# iiitduino.net
KiCad netlist of a schematic drawn in EAGLE
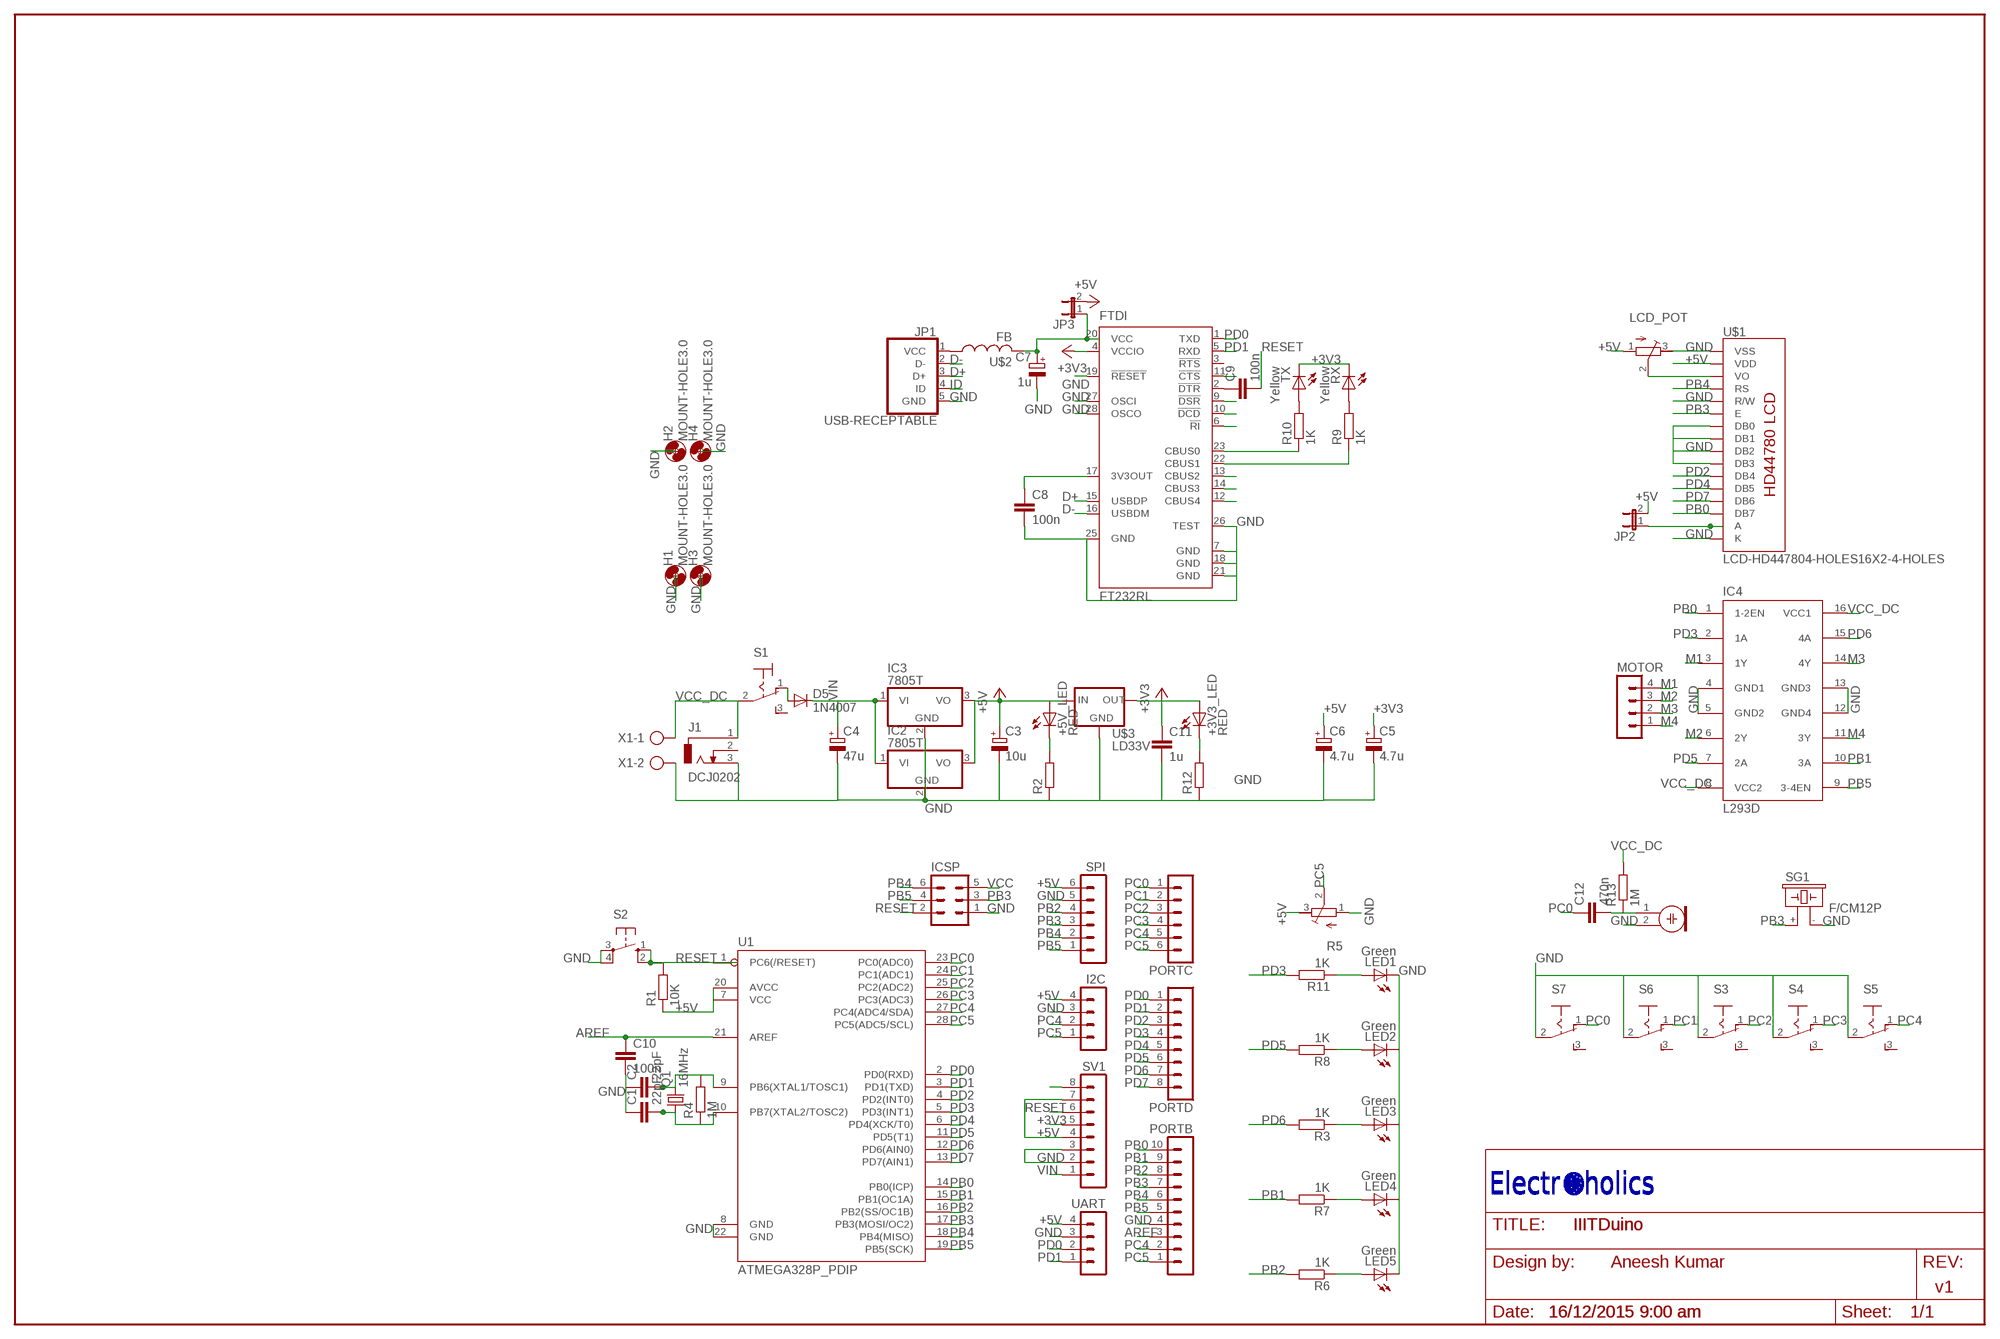
[diagram p0: schematic, sheet 1]

(export (version "E")
  (design (tool "Eeschema 10.0.6"))
  (components
    (comp (ref "+3V3_LED")
      (value "RED")
      (footprint "eagle-import:LED3MM")
      (libsource (lib "eagle-import") (part "LED3MM"))
    )
    (comp (ref "+5V_LED")
      (value "RED")
      (footprint "eagle-import:LED3MM")
      (libsource (lib "eagle-import") (part "LED3MM"))
    )
    (comp (ref "C1")
      (value "22pF")
      (footprint "eagle-import:C025-025X050")
      (libsource (lib "eagle-import") (part "C-EU025-025X050"))
    )
    (comp (ref "C2")
      (value "22pF")
      (footprint "eagle-import:C025-025X050")
      (libsource (lib "eagle-import") (part "C-EU025-025X050"))
    )
    (comp (ref "C3")
      (value "10u")
      (footprint "eagle-import:E2,5-6")
      (libsource (lib "eagle-import") (part "CPOL-EUE2.5-6"))
    )
    (comp (ref "C4")
      (value "47u")
      (footprint "eagle-import:E5-10,5")
      (libsource (lib "eagle-import") (part "CPOL-EUE5-10.5"))
    )
    (comp (ref "C5")
      (value "4.7u")
      (footprint "eagle-import:E2,5-6")
      (libsource (lib "eagle-import") (part "CPOL-EUE2.5-6"))
    )
    (comp (ref "C6")
      (value "4.7u")
      (footprint "eagle-import:E2,5-6")
      (libsource (lib "eagle-import") (part "CPOL-EUE2.5-6"))
    )
    (comp (ref "C7")
      (value "1u")
      (footprint "eagle-import:E2,5-6")
      (libsource (lib "eagle-import") (part "CPOL-EUE2.5-6"))
    )
    (comp (ref "C8")
      (value "100n")
      (footprint "eagle-import:C025-025X050")
      (libsource (lib "eagle-import") (part "C-EU025-025X050"))
    )
    (comp (ref "C9")
      (value "100n")
      (footprint "eagle-import:C025-025X050")
      (libsource (lib "eagle-import") (part "C-EU025-025X050"))
    )
    (comp (ref "C10")
      (value "100n")
      (footprint "eagle-import:C025-025X050")
      (libsource (lib "eagle-import") (part "C-EU025-025X050"))
    )
    (comp (ref "C11")
      (value "1u")
      (footprint "eagle-import:C025-025X050")
      (libsource (lib "eagle-import") (part "C-EU025-025X050"))
    )
    (comp (ref "C12")
      (value "470n")
      (footprint "eagle-import:C025-025X050")
      (libsource (lib "eagle-import") (part "C-EU025-025X050"))
    )
    (comp (ref "D5")
      (value "1N4007")
      (footprint "eagle-import:DO41-10")
      (libsource (lib "eagle-import") (part "1N4004"))
    )
    (comp (ref "FTDI")
      (value "FT232RL")
      (footprint "eagle-import:SSOP28")
      (libsource (lib "eagle-import") (part "FT232RL"))
    )
    (comp (ref "H1")
      (value "MOUNT-HOLE3.0")
      (footprint "eagle-import:3,0")
      (libsource (lib "eagle-import") (part "MOUNT-HOLE3.0"))
    )
    (comp (ref "H2")
      (value "MOUNT-HOLE3.0")
      (footprint "eagle-import:3,0")
      (libsource (lib "eagle-import") (part "MOUNT-HOLE3.0"))
    )
    (comp (ref "H3")
      (value "MOUNT-HOLE3.0")
      (footprint "eagle-import:3,0")
      (libsource (lib "eagle-import") (part "MOUNT-HOLE3.0"))
    )
    (comp (ref "H4")
      (value "MOUNT-HOLE3.0")
      (footprint "eagle-import:3,0")
      (libsource (lib "eagle-import") (part "MOUNT-HOLE3.0"))
    )
    (comp (ref "I2C")
      (value "MA04-1")
      (footprint "eagle-import:MA04-1")
      (libsource (lib "eagle-import") (part "MA04-1"))
    )
    (comp (ref "IC2")
      (value "7805T")
      (footprint "eagle-import:TO220H")
      (libsource (lib "eagle-import") (part "78T05"))
    )
    (comp (ref "IC3")
      (value "7805T")
      (footprint "eagle-import:TO220H")
      (libsource (lib "eagle-import") (part "78T05"))
    )
    (comp (ref "IC4")
      (value "L293D")
      (footprint "eagle-import:DIL16")
      (libsource (lib "eagle-import") (part "L293D"))
    )
    (comp (ref "ICSP")
      (value "MA03-2")
      (footprint "eagle-import:MA03-2")
      (libsource (lib "eagle-import") (part "MA03-2"))
    )
    (comp (ref "J1")
      (value "DCJ0202")
      (footprint "eagle-import:DCJ0202")
      (libsource (lib "eagle-import") (part "DCJ0202"))
    )
    (comp (ref "JP1")
      (value "USB-RECEPTABLE")
      (footprint "eagle-import:FCI-10103594-0001LF")
      (libsource (lib "eagle-import") (part "USB-RECEPTABLE"))
    )
    (comp (ref "JP2")
      (value "JP1E")
      (footprint "eagle-import:JP1")
      (libsource (lib "eagle-import") (part "JP1E"))
    )
    (comp (ref "JP3")
      (value "JP1E")
      (footprint "eagle-import:JP1")
      (libsource (lib "eagle-import") (part "JP1E"))
    )
    (comp (ref "LCD_POT")
      (value "R-TRIMM64W")
      (footprint "eagle-import:RTRIM64W")
      (libsource (lib "eagle-import") (part "R-TRIMM64W"))
    )
    (comp (ref "LED1")
      (value "Green")
      (footprint "eagle-import:LED3MM")
      (libsource (lib "eagle-import") (part "LED3MM"))
    )
    (comp (ref "LED2")
      (value "Green")
      (footprint "eagle-import:LED3MM")
      (libsource (lib "eagle-import") (part "LED3MM"))
    )
    (comp (ref "LED3")
      (value "Green")
      (footprint "eagle-import:LED3MM")
      (libsource (lib "eagle-import") (part "LED3MM"))
    )
    (comp (ref "LED4")
      (value "Green")
      (footprint "eagle-import:LED3MM")
      (libsource (lib "eagle-import") (part "LED3MM"))
    )
    (comp (ref "LED5")
      (value "Green")
      (footprint "eagle-import:LED3MM")
      (libsource (lib "eagle-import") (part "LED3MM"))
    )
    (comp (ref "M1")
      (value "ELECTRET_MICROPHON-F6050AP")
      (footprint "eagle-import:F6050AP")
      (libsource (lib "eagle-import") (part "ELECTRET_MICROPHON-F6050AP"))
    )
    (comp (ref "MOTOR")
      (value "MA04-1")
      (footprint "eagle-import:MA04-1")
      (libsource (lib "eagle-import") (part "MA04-1"))
    )
    (comp (ref "PORTB")
      (value "MA10-1W")
      (footprint "eagle-import:MA10-1W")
      (libsource (lib "eagle-import") (part "MA10-1W"))
    )
    (comp (ref "PORTC")
      (value "MA06-1")
      (footprint "eagle-import:MA06-1")
      (libsource (lib "eagle-import") (part "MA06-1"))
    )
    (comp (ref "PORTD")
      (value "MA08-1")
      (footprint "eagle-import:MA08-1")
      (libsource (lib "eagle-import") (part "MA08-1"))
    )
    (comp (ref "Q1")
      (value "16MHz")
      (footprint "eagle-import:HC49U70")
      (libsource (lib "eagle-import") (part "CRYSTALHC49U70"))
    )
    (comp (ref "R1")
      (value "10K")
      (footprint "eagle-import:0207_10")
      (libsource (lib "eagle-import") (part "R-EU_0207/10"))
    )
    (comp (ref "R2")
      (value "R-EU_0207/7")
      (footprint "eagle-import:0207_7")
      (libsource (lib "eagle-import") (part "R-EU_0207/7"))
    )
    (comp (ref "R3")
      (value "1K")
      (footprint "eagle-import:0207_10")
      (libsource (lib "eagle-import") (part "R-EU_0207/10"))
    )
    (comp (ref "R4")
      (value "1M")
      (footprint "eagle-import:0207_10")
      (libsource (lib "eagle-import") (part "R-EU_0207/10"))
    )
    (comp (ref "R5")
      (value "R-TRIMM64W")
      (footprint "eagle-import:RTRIM64W")
      (libsource (lib "eagle-import") (part "R-TRIMM64W"))
    )
    (comp (ref "R6")
      (value "1K")
      (footprint "eagle-import:0207_10")
      (libsource (lib "eagle-import") (part "R-EU_0207/10"))
    )
    (comp (ref "R7")
      (value "1K")
      (footprint "eagle-import:0207_10")
      (libsource (lib "eagle-import") (part "R-EU_0207/10"))
    )
    (comp (ref "R8")
      (value "1K")
      (footprint "eagle-import:0207_10")
      (libsource (lib "eagle-import") (part "R-EU_0207/10"))
    )
    (comp (ref "R9")
      (value "1K")
      (footprint "eagle-import:0207_7")
      (libsource (lib "eagle-import") (part "R-EU_0207/7"))
    )
    (comp (ref "R10")
      (value "1K")
      (footprint "eagle-import:0207_7")
      (libsource (lib "eagle-import") (part "R-EU_0207/7"))
    )
    (comp (ref "R11")
      (value "1K")
      (footprint "eagle-import:0207_10")
      (libsource (lib "eagle-import") (part "R-EU_0207/10"))
    )
    (comp (ref "R12")
      (value "R-EU_0207/7")
      (footprint "eagle-import:0207_7")
      (libsource (lib "eagle-import") (part "R-EU_0207/7"))
    )
    (comp (ref "R13")
      (value "1M")
      (footprint "eagle-import:0207_10")
      (libsource (lib "eagle-import") (part "R-EU_0207/10"))
    )
    (comp (ref "RX")
      (value "Yellow")
      (footprint "eagle-import:LED3MM")
      (libsource (lib "eagle-import") (part "LED3MM"))
    )
    (comp (ref "S1")
      (value "320-916")
      (footprint "eagle-import:320-916")
      (libsource (lib "eagle-import") (part "320-916"))
    )
    (comp (ref "S2")
      (value "10-XX")
      (footprint "eagle-import:B3F-10XX")
      (fields (field (name "MPN") "B3F-1000"))
      (libsource (lib "eagle-import") (part "10-XX"))
    )
    (comp (ref "S3")
      (value "255SB")
      (footprint "eagle-import:255SB")
      (libsource (lib "eagle-import") (part "255SB"))
    )
    (comp (ref "S4")
      (value "255SB")
      (footprint "eagle-import:255SB")
      (libsource (lib "eagle-import") (part "255SB"))
    )
    (comp (ref "S5")
      (value "255SB")
      (footprint "eagle-import:255SB")
      (libsource (lib "eagle-import") (part "255SB"))
    )
    (comp (ref "S6")
      (value "255SB")
      (footprint "eagle-import:255SB")
      (libsource (lib "eagle-import") (part "255SB"))
    )
    (comp (ref "S7")
      (value "255SB")
      (footprint "eagle-import:255SB")
      (libsource (lib "eagle-import") (part "255SB"))
    )
    (comp (ref "SG1")
      (value "F/CM12P")
      (footprint "eagle-import:F_CM12P")
      (libsource (lib "eagle-import") (part "F/CM12P"))
    )
    (comp (ref "SPI")
      (value "MA06-1")
      (footprint "eagle-import:MA06-1")
      (libsource (lib "eagle-import") (part "MA06-1"))
    )
    (comp (ref "SV1")
      (value "MA08-1")
      (footprint "eagle-import:MA08-1")
      (libsource (lib "eagle-import") (part "MA08-1"))
    )
    (comp (ref "TX")
      (value "Yellow")
      (footprint "eagle-import:LED3MM")
      (libsource (lib "eagle-import") (part "LED3MM"))
    )
    (comp (ref "U$1")
      (value "LCD-HD447804-HOLES16X2-4-HOLES")
      (footprint "eagle-import:LCD-16X2-4HOLES")
      (libsource (lib "eagle-import") (part "LCD-HD4478016X2-4-HOLES4-HOLES"))
    )
    (comp (ref "U$2") (value "FB") (footprint "eagle-import:FB") (libsource (lib "eagle-import") (part "FB")))
    (comp (ref "U$3")
      (value "LD33V")
      (footprint "eagle-import:TO-220")
      (libsource (lib "eagle-import") (part "LD33V"))
    )
    (comp (ref "U1")
      (value "ATMEGA328P_PDIP")
      (footprint "eagle-import:DIL28-3")
      (libsource (lib "eagle-import") (part "ATMEGA328P_PDIP"))
    )
    (comp (ref "UART")
      (value "MA04-1")
      (footprint "eagle-import:MA04-1")
      (libsource (lib "eagle-import") (part "MA04-1"))
    )
    (comp (ref "X1")
      (value "AK300/2")
      (footprint "eagle-import:AK300_2")
      (libsource (lib "eagle-import") (part "AK300/2"))
    )
  )
  (nets
    (net (code "1") (name "+3V3") (class "Default")
      (node (ref "+3V3_LED") (pin "A") (pinfunction "A_A") (pintype "passive"))
      (node (ref "C11") (pin "1") (pinfunction "1_1") (pintype "passive"))
      (node (ref "C5") (pin "+") (pinfunction "+_+") (pintype "passive"))
      (node (ref "FTDI") (pin "4") (pinfunction "VCCIO_4") (pintype "power_in"))
      (node (ref "RX") (pin "K") (pinfunction "C_K") (pintype "passive"))
      (node (ref "SV1") (pin "5") (pinfunction "5_5") (pintype "passive"))
      (node (ref "TX") (pin "K") (pinfunction "C_K") (pintype "passive"))
      (node (ref "U$3") (pin "2") (pinfunction "OUT_2") (pintype "passive"))
    )
    (net (code "2") (name "+5V") (class "Default")
      (node (ref "+5V_LED") (pin "A") (pinfunction "A_A") (pintype "passive"))
      (node (ref "C3") (pin "+") (pinfunction "+_+") (pintype "passive"))
      (node (ref "C6") (pin "+") (pinfunction "+_+") (pintype "passive"))
      (node (ref "C7") (pin "+") (pinfunction "+_+") (pintype "passive"))
      (node (ref "FTDI") (pin "20") (pinfunction "VCC_20") (pintype "power_in"))
      (node (ref "I2C") (pin "4") (pinfunction "4_4") (pintype "passive"))
      (node (ref "IC2") (pin "3") (pinfunction "VO_3") (pintype "passive"))
      (node (ref "IC3") (pin "3") (pinfunction "VO_3") (pintype "passive"))
      (node (ref "JP2") (pin "2") (pinfunction "2_2") (pintype "passive"))
      (node (ref "JP3") (pin "1") (pinfunction "1_1") (pintype "passive"))
      (node (ref "JP3") (pin "2") (pinfunction "2_2") (pintype "passive"))
      (node (ref "LCD_POT") (pin "1") (pinfunction "A_1") (pintype "passive"))
      (node (ref "R1") (pin "1") (pinfunction "1_1") (pintype "passive"))
      (node (ref "R5") (pin "3") (pinfunction "E_3") (pintype "passive"))
      (node (ref "SPI") (pin "6") (pinfunction "6_6") (pintype "passive"))
      (node (ref "SV1") (pin "4") (pinfunction "4_4") (pintype "passive"))
      (node (ref "SV1") (pin "7") (pinfunction "7_7") (pintype "passive"))
      (node (ref "U$1") (pin "2") (pinfunction "VDD_2") (pintype "power_in"))
      (node (ref "U$2") (pin "P$2") (pinfunction "2_P$2") (pintype "passive"))
      (node (ref "U$3") (pin "3") (pinfunction "IN_3") (pintype "input"))
      (node (ref "U1") (pin "20") (pinfunction "AVCC_20") (pintype "bidirectional"))
      (node (ref "U1") (pin "7") (pinfunction "VCC_7") (pintype "bidirectional"))
      (node (ref "UART") (pin "4") (pinfunction "4_4") (pintype "passive"))
    )
    (net (code "3") (name "/AREF") (class "Default")
      (node (ref "C10") (pin "1") (pinfunction "1_1") (pintype "passive"))
      (node (ref "PORTB") (pin "3") (pinfunction "3_3") (pintype "passive"))
      (node (ref "U1") (pin "21") (pinfunction "AREF_21") (pintype "bidirectional"))
    )
    (net (code "4") (name "/D+") (class "Default")
      (node (ref "FTDI") (pin "15") (pinfunction "USBDP_15") (pintype "bidirectional"))
      (node (ref "JP1") (pin "3") (pinfunction "D+_3") (pintype "bidirectional"))
    )
    (net (code "5") (name "/D-") (class "Default")
      (node (ref "FTDI") (pin "16") (pinfunction "USBDM_16") (pintype "bidirectional"))
      (node (ref "JP1") (pin "2") (pinfunction "D-_2") (pintype "bidirectional"))
    )
    (net (code "6") (name "/GND") (class "Default")
      (node (ref "C1") (pin "1") (pinfunction "1_1") (pintype "passive"))
      (node (ref "C10") (pin "2") (pinfunction "2_2") (pintype "passive"))
      (node (ref "C11") (pin "2") (pinfunction "2_2") (pintype "passive"))
      (node (ref "C2") (pin "1") (pinfunction "1_1") (pintype "passive"))
      (node (ref "C3") (pin "-") (pinfunction "-_-") (pintype "passive"))
      (node (ref "C4") (pin "-") (pinfunction "-_-") (pintype "passive"))
      (node (ref "C5") (pin "-") (pinfunction "-_-") (pintype "passive"))
      (node (ref "C6") (pin "-") (pinfunction "-_-") (pintype "passive"))
      (node (ref "C7") (pin "-") (pinfunction "-_-") (pintype "passive"))
      (node (ref "C8") (pin "2") (pinfunction "2_2") (pintype "passive"))
      (node (ref "FTDI") (pin "10") (pinfunction "~{DCD}_10") (pintype "input"))
      (node (ref "FTDI") (pin "11") (pinfunction "~{CTS}_11") (pintype "input"))
      (node (ref "FTDI") (pin "12") (pinfunction "CBUS4_12") (pintype "bidirectional"))
      (node (ref "FTDI") (pin "13") (pinfunction "CBUS2_13") (pintype "bidirectional"))
      (node (ref "FTDI") (pin "14") (pinfunction "CBUS3_14") (pintype "bidirectional"))
      (node (ref "FTDI") (pin "18") (pinfunction "GND_18") (pintype "power_in"))
      (node (ref "FTDI") (pin "19") (pinfunction "~{RESET}_19") (pintype "input"))
      (node (ref "FTDI") (pin "21") (pinfunction "GND_21") (pintype "power_in"))
      (node (ref "FTDI") (pin "25") (pinfunction "GND_25") (pintype "power_in"))
      (node (ref "FTDI") (pin "26") (pinfunction "TEST_26") (pintype "input"))
      (node (ref "FTDI") (pin "27") (pinfunction "OSCI_27") (pintype "input"))
      (node (ref "FTDI") (pin "28") (pinfunction "OSCO_28") (pintype "output"))
      (node (ref "FTDI") (pin "6") (pinfunction "~{RI}_6") (pintype "input"))
      (node (ref "FTDI") (pin "7") (pinfunction "GND_7") (pintype "power_in"))
      (node (ref "FTDI") (pin "9") (pinfunction "~{DSR}_9") (pintype "input"))
      (node (ref "I2C") (pin "3") (pinfunction "3_3") (pintype "passive"))
      (node (ref "IC2") (pin "2") (pinfunction "GND_2") (pintype "passive"))
      (node (ref "IC3") (pin "2") (pinfunction "GND_2") (pintype "passive"))
      (node (ref "IC4") (pin "12") (pinfunction "GND4_12") (pintype "power_in"))
      (node (ref "IC4") (pin "13") (pinfunction "GND3_13") (pintype "power_in"))
      (node (ref "IC4") (pin "4") (pinfunction "GND1_4") (pintype "power_in"))
      (node (ref "IC4") (pin "5") (pinfunction "GND2_5") (pintype "power_in"))
      (node (ref "ICSP") (pin "1") (pinfunction "1_1") (pintype "passive"))
      (node (ref "J1") (pin "3") (pinfunction "3_3") (pintype "passive"))
      (node (ref "JP1") (pin "5") (pinfunction "GND_5") (pintype "bidirectional"))
      (node (ref "LCD_POT") (pin "3") (pinfunction "E_3") (pintype "passive"))
      (node (ref "LED1") (pin "K") (pinfunction "C_K") (pintype "passive"))
      (node (ref "LED2") (pin "K") (pinfunction "C_K") (pintype "passive"))
      (node (ref "LED3") (pin "K") (pinfunction "C_K") (pintype "passive"))
      (node (ref "LED4") (pin "K") (pinfunction "C_K") (pintype "passive"))
      (node (ref "LED5") (pin "K") (pinfunction "C_K") (pintype "passive"))
      (node (ref "M1") (pin "2") (pinfunction "2_2") (pintype "passive"))
      (node (ref "PORTB") (pin "4") (pinfunction "4_4") (pintype "passive"))
      (node (ref "R12") (pin "1") (pinfunction "1_1") (pintype "passive"))
      (node (ref "R2") (pin "1") (pinfunction "1_1") (pintype "passive"))
      (node (ref "R5") (pin "1") (pinfunction "A_1") (pintype "passive"))
      (node (ref "S2") (pin "3") (pinfunction "P_3") (pintype "passive"))
      (node (ref "S2") (pin "4") (pinfunction "P1_4") (pintype "passive"))
      (node (ref "S3") (pin "2") (pinfunction "P_2") (pintype "passive"))
      (node (ref "S4") (pin "2") (pinfunction "P_2") (pintype "passive"))
      (node (ref "S5") (pin "2") (pinfunction "P_2") (pintype "passive"))
      (node (ref "S6") (pin "2") (pinfunction "P_2") (pintype "passive"))
      (node (ref "S7") (pin "2") (pinfunction "P_2") (pintype "passive"))
      (node (ref "SG1") (pin "-") (pinfunction "2_-") (pintype "passive"))
      (node (ref "SPI") (pin "5") (pinfunction "5_5") (pintype "passive"))
      (node (ref "SV1") (pin "2") (pinfunction "2_2") (pintype "passive"))
      (node (ref "SV1") (pin "3") (pinfunction "3_3") (pintype "passive"))
      (node (ref "U$1") (pin "1") (pinfunction "VSS_1") (pintype "power_in"))
      (node (ref "U$1") (pin "10") (pinfunction "DB3_10") (pintype "bidirectional"))
      (node (ref "U$1") (pin "16") (pinfunction "K_16") (pintype "power_in"))
      (node (ref "U$1") (pin "5") (pinfunction "R/W_5") (pintype "input"))
      (node (ref "U$1") (pin "7") (pinfunction "DB0_7") (pintype "bidirectional"))
      (node (ref "U$1") (pin "8") (pinfunction "DB1_8") (pintype "bidirectional"))
      (node (ref "U$1") (pin "9") (pinfunction "DB2_9") (pintype "bidirectional"))
      (node (ref "U$3") (pin "1") (pinfunction "GND_1") (pintype "input"))
      (node (ref "U1") (pin "22") (pinfunction "GND_22") (pintype "bidirectional"))
      (node (ref "U1") (pin "8") (pinfunction "GND_8") (pintype "bidirectional"))
      (node (ref "UART") (pin "3") (pinfunction "3_3") (pintype "passive"))
      (node (ref "X1") (pin "2") (pinfunction "KL_2") (pintype "passive"))
    )
    (net (code "7") (name "/ID") (class "Default")
      (node (ref "JP1") (pin "4") (pinfunction "ID_4") (pintype "bidirectional"))
    )
    (net (code "8") (name "/M1") (class "Default")
      (node (ref "IC4") (pin "3") (pinfunction "1Y_3") (pintype "output"))
      (node (ref "MOTOR") (pin "4") (pinfunction "4_4") (pintype "passive"))
    )
    (net (code "9") (name "/M2") (class "Default")
      (node (ref "IC4") (pin "6") (pinfunction "2Y_6") (pintype "output"))
      (node (ref "MOTOR") (pin "3") (pinfunction "3_3") (pintype "passive"))
    )
    (net (code "10") (name "/M3") (class "Default")
      (node (ref "IC4") (pin "14") (pinfunction "4Y_14") (pintype "output"))
      (node (ref "MOTOR") (pin "2") (pinfunction "2_2") (pintype "passive"))
    )
    (net (code "11") (name "/M4") (class "Default")
      (node (ref "IC4") (pin "11") (pinfunction "3Y_11") (pintype "output"))
      (node (ref "MOTOR") (pin "1") (pinfunction "1_1") (pintype "passive"))
    )
    (net (code "12") (name "/PB0") (class "Default")
      (node (ref "IC4") (pin "1") (pinfunction "1-2EN_1") (pintype "input"))
      (node (ref "PORTB") (pin "10") (pinfunction "10_10") (pintype "passive"))
      (node (ref "U$1") (pin "14") (pinfunction "DB7_14") (pintype "bidirectional"))
      (node (ref "U1") (pin "14") (pinfunction "PB0(ICP)_14") (pintype "bidirectional"))
    )
    (net (code "13") (name "/PB1") (class "Default")
      (node (ref "IC4") (pin "10") (pinfunction "3A_10") (pintype "input"))
      (node (ref "PORTB") (pin "9") (pinfunction "9_9") (pintype "passive"))
      (node (ref "R7") (pin "2") (pinfunction "2_2") (pintype "passive"))
      (node (ref "U1") (pin "15") (pinfunction "PB1(OC1A)_15") (pintype "bidirectional"))
    )
    (net (code "14") (name "/PB2") (class "Default")
      (node (ref "PORTB") (pin "8") (pinfunction "8_8") (pintype "passive"))
      (node (ref "R6") (pin "2") (pinfunction "2_2") (pintype "passive"))
      (node (ref "SPI") (pin "4") (pinfunction "4_4") (pintype "passive"))
      (node (ref "U1") (pin "16") (pinfunction "PB2(SS/OC1B)_16") (pintype "bidirectional"))
    )
    (net (code "15") (name "/PB3") (class "Default")
      (node (ref "ICSP") (pin "3") (pinfunction "3_3") (pintype "passive"))
      (node (ref "PORTB") (pin "7") (pinfunction "7_7") (pintype "passive"))
      (node (ref "SG1") (pin "+") (pinfunction "1_+") (pintype "passive"))
      (node (ref "SPI") (pin "3") (pinfunction "3_3") (pintype "passive"))
      (node (ref "U$1") (pin "6") (pinfunction "E_6") (pintype "input"))
      (node (ref "U1") (pin "17") (pinfunction "PB3(MOSI/OC2)_17") (pintype "bidirectional"))
    )
    (net (code "16") (name "/PB4") (class "Default")
      (node (ref "ICSP") (pin "6") (pinfunction "6_6") (pintype "passive"))
      (node (ref "PORTB") (pin "6") (pinfunction "6_6") (pintype "passive"))
      (node (ref "SPI") (pin "2") (pinfunction "2_2") (pintype "passive"))
      (node (ref "U$1") (pin "4") (pinfunction "RS_4") (pintype "input"))
      (node (ref "U1") (pin "18") (pinfunction "PB4(MISO)_18") (pintype "bidirectional"))
    )
    (net (code "17") (name "/PB5") (class "Default")
      (node (ref "IC4") (pin "9") (pinfunction "3-4EN_9") (pintype "input"))
      (node (ref "ICSP") (pin "4") (pinfunction "4_4") (pintype "passive"))
      (node (ref "PORTB") (pin "5") (pinfunction "5_5") (pintype "passive"))
      (node (ref "SPI") (pin "1") (pinfunction "1_1") (pintype "passive"))
      (node (ref "U1") (pin "19") (pinfunction "PB5(SCK)_19") (pintype "bidirectional"))
    )
    (net (code "18") (name "/PC0") (class "Default")
      (node (ref "C12") (pin "1") (pinfunction "1_1") (pintype "passive"))
      (node (ref "PORTC") (pin "1") (pinfunction "1_1") (pintype "passive"))
      (node (ref "S7") (pin "1") (pinfunction "O_1") (pintype "passive"))
      (node (ref "U1") (pin "23") (pinfunction "PC0(ADC0)_23") (pintype "bidirectional"))
    )
    (net (code "19") (name "/PC1") (class "Default")
      (node (ref "PORTC") (pin "2") (pinfunction "2_2") (pintype "passive"))
      (node (ref "S6") (pin "1") (pinfunction "O_1") (pintype "passive"))
      (node (ref "U1") (pin "24") (pinfunction "PC1(ADC1)_24") (pintype "bidirectional"))
    )
    (net (code "20") (name "/PC2") (class "Default")
      (node (ref "PORTC") (pin "3") (pinfunction "3_3") (pintype "passive"))
      (node (ref "S3") (pin "1") (pinfunction "O_1") (pintype "passive"))
      (node (ref "U1") (pin "25") (pinfunction "PC2(ADC2)_25") (pintype "bidirectional"))
    )
    (net (code "21") (name "/PC3") (class "Default")
      (node (ref "PORTC") (pin "4") (pinfunction "4_4") (pintype "passive"))
      (node (ref "S4") (pin "1") (pinfunction "O_1") (pintype "passive"))
      (node (ref "U1") (pin "26") (pinfunction "PC3(ADC3)_26") (pintype "bidirectional"))
    )
    (net (code "22") (name "/PC4") (class "Default")
      (node (ref "I2C") (pin "2") (pinfunction "2_2") (pintype "passive"))
      (node (ref "PORTB") (pin "2") (pinfunction "2_2") (pintype "passive"))
      (node (ref "PORTC") (pin "5") (pinfunction "5_5") (pintype "passive"))
      (node (ref "S5") (pin "1") (pinfunction "O_1") (pintype "passive"))
      (node (ref "U1") (pin "27") (pinfunction "PC4(ADC4/SDA)_27") (pintype "bidirectional"))
    )
    (net (code "23") (name "/PC5") (class "Default")
      (node (ref "I2C") (pin "1") (pinfunction "1_1") (pintype "passive"))
      (node (ref "PORTB") (pin "1") (pinfunction "1_1") (pintype "passive"))
      (node (ref "PORTC") (pin "6") (pinfunction "6_6") (pintype "passive"))
      (node (ref "R5") (pin "2") (pinfunction "S_2") (pintype "passive"))
      (node (ref "U1") (pin "28") (pinfunction "PC5(ADC5/SCL)_28") (pintype "bidirectional"))
    )
    (net (code "24") (name "/PD0") (class "Default")
      (node (ref "FTDI") (pin "1") (pinfunction "TXD_1") (pintype "output"))
      (node (ref "PORTD") (pin "1") (pinfunction "1_1") (pintype "passive"))
      (node (ref "U1") (pin "2") (pinfunction "PD0(RXD)_2") (pintype "bidirectional"))
      (node (ref "UART") (pin "2") (pinfunction "2_2") (pintype "passive"))
    )
    (net (code "25") (name "/PD1") (class "Default")
      (node (ref "FTDI") (pin "5") (pinfunction "RXD_5") (pintype "input"))
      (node (ref "PORTD") (pin "2") (pinfunction "2_2") (pintype "passive"))
      (node (ref "U1") (pin "3") (pinfunction "PD1(TXD)_3") (pintype "bidirectional"))
      (node (ref "UART") (pin "1") (pinfunction "1_1") (pintype "passive"))
    )
    (net (code "26") (name "/PD2") (class "Default")
      (node (ref "PORTD") (pin "3") (pinfunction "3_3") (pintype "passive"))
      (node (ref "U$1") (pin "11") (pinfunction "DB4_11") (pintype "bidirectional"))
      (node (ref "U1") (pin "4") (pinfunction "PD2(INT0)_4") (pintype "bidirectional"))
    )
    (net (code "27") (name "/PD3") (class "Default")
      (node (ref "IC4") (pin "2") (pinfunction "1A_2") (pintype "input"))
      (node (ref "PORTD") (pin "4") (pinfunction "4_4") (pintype "passive"))
      (node (ref "R11") (pin "2") (pinfunction "2_2") (pintype "passive"))
      (node (ref "U1") (pin "5") (pinfunction "PD3(INT1)_5") (pintype "bidirectional"))
    )
    (net (code "28") (name "/PD4") (class "Default")
      (node (ref "PORTD") (pin "5") (pinfunction "5_5") (pintype "passive"))
      (node (ref "U$1") (pin "12") (pinfunction "DB5_12") (pintype "bidirectional"))
      (node (ref "U1") (pin "6") (pinfunction "PD4(XCK/T0)_6") (pintype "bidirectional"))
    )
    (net (code "29") (name "/PD5") (class "Default")
      (node (ref "IC4") (pin "7") (pinfunction "2A_7") (pintype "input"))
      (node (ref "PORTD") (pin "6") (pinfunction "6_6") (pintype "passive"))
      (node (ref "R8") (pin "2") (pinfunction "2_2") (pintype "passive"))
      (node (ref "U1") (pin "11") (pinfunction "PD5(T1)_11") (pintype "bidirectional"))
    )
    (net (code "30") (name "/PD6") (class "Default")
      (node (ref "IC4") (pin "15") (pinfunction "4A_15") (pintype "input"))
      (node (ref "PORTD") (pin "7") (pinfunction "7_7") (pintype "passive"))
      (node (ref "R3") (pin "2") (pinfunction "2_2") (pintype "passive"))
      (node (ref "U1") (pin "12") (pinfunction "PD6(AIN0)_12") (pintype "bidirectional"))
    )
    (net (code "31") (name "/PD7") (class "Default")
      (node (ref "PORTD") (pin "8") (pinfunction "8_8") (pintype "passive"))
      (node (ref "U$1") (pin "13") (pinfunction "DB6_13") (pintype "bidirectional"))
      (node (ref "U1") (pin "13") (pinfunction "PD7(AIN1)_13") (pintype "bidirectional"))
    )
    (net (code "32") (name "/RESET") (class "Default")
      (node (ref "C9") (pin "2") (pinfunction "2_2") (pintype "passive"))
      (node (ref "ICSP") (pin "2") (pinfunction "2_2") (pintype "passive"))
      (node (ref "R1") (pin "2") (pinfunction "2_2") (pintype "passive"))
      (node (ref "S2") (pin "1") (pinfunction "S_1") (pintype "passive"))
      (node (ref "S2") (pin "2") (pinfunction "S1_2") (pintype "passive"))
      (node (ref "SV1") (pin "6") (pinfunction "6_6") (pintype "passive"))
    )
    (net (code "33") (name "/VCC") (class "Default")
      (node (ref "ICSP") (pin "5") (pinfunction "5_5") (pintype "passive"))
    )
    (net (code "34") (name "/VCC_DC") (class "Default")
      (node (ref "IC4") (pin "16") (pinfunction "VCC1_16") (pintype "power_in"))
      (node (ref "IC4") (pin "8") (pinfunction "VCC2_8") (pintype "power_in"))
      (node (ref "J1") (pin "1") (pinfunction "1_1") (pintype "passive"))
      (node (ref "R13") (pin "2") (pinfunction "2_2") (pintype "passive"))
      (node (ref "S1") (pin "2") (pinfunction "P_2") (pintype "passive"))
      (node (ref "X1") (pin "1") (pinfunction "KL_1") (pintype "passive"))
    )
    (net (code "35") (name "/VIN") (class "Default")
      (node (ref "C4") (pin "+") (pinfunction "+_+") (pintype "passive"))
      (node (ref "D5") (pin "C") (pinfunction "C_C") (pintype "passive"))
      (node (ref "IC2") (pin "1") (pinfunction "VI_1") (pintype "input"))
      (node (ref "IC3") (pin "1") (pinfunction "VI_1") (pintype "input"))
      (node (ref "SV1") (pin "1") (pinfunction "1_1") (pintype "passive"))
    )
    (net (code "36") (name "Net-(+3V3_LED-C)") (class "Default")
      (node (ref "+3V3_LED") (pin "K") (pinfunction "C_K") (pintype "passive"))
      (node (ref "R12") (pin "2") (pinfunction "2_2") (pintype "passive"))
    )
    (net (code "37") (name "Net-(+5V_LED-C)") (class "Default")
      (node (ref "+5V_LED") (pin "K") (pinfunction "C_K") (pintype "passive"))
      (node (ref "R2") (pin "2") (pinfunction "2_2") (pintype "passive"))
    )
    (net (code "38") (name "Net-(C12-Pad2)") (class "Default")
      (node (ref "C12") (pin "2") (pinfunction "2_2") (pintype "passive"))
      (node (ref "M1") (pin "1") (pinfunction "1_1") (pintype "passive"))
      (node (ref "R13") (pin "1") (pinfunction "1_1") (pintype "passive"))
    )
    (net (code "39") (name "Net-(FTDI-3V3OUT)") (class "Default")
      (node (ref "C8") (pin "1") (pinfunction "1_1") (pintype "passive"))
      (node (ref "FTDI") (pin "17") (pinfunction "3V3OUT_17") (pintype "output"))
    )
    (net (code "40") (name "Net-(FTDI-CBUS0)") (class "Default")
      (node (ref "FTDI") (pin "23") (pinfunction "CBUS0_23") (pintype "bidirectional"))
      (node (ref "R10") (pin "1") (pinfunction "1_1") (pintype "passive"))
    )
    (net (code "41") (name "Net-(FTDI-CBUS1)") (class "Default")
      (node (ref "FTDI") (pin "22") (pinfunction "CBUS1_22") (pintype "bidirectional"))
      (node (ref "R9") (pin "1") (pinfunction "1_1") (pintype "passive"))
    )
    (net (code "42") (name "Net-(FTDI-~{DTR})") (class "Default")
      (node (ref "C9") (pin "1") (pinfunction "1_1") (pintype "passive"))
      (node (ref "FTDI") (pin "2") (pinfunction "~{DTR}_2") (pintype "output"))
    )
    (net (code "43") (name "Net-(JP1-VCC)") (class "Default")
      (node (ref "JP1") (pin "1") (pinfunction "VCC_1") (pintype "bidirectional"))
      (node (ref "U$2") (pin "P$1") (pinfunction "1_P$1") (pintype "passive"))
    )
    (net (code "44") (name "Net-(LCD_POT-S)") (class "Default")
      (node (ref "LCD_POT") (pin "2") (pinfunction "S_2") (pintype "passive"))
      (node (ref "U$1") (pin "3") (pinfunction "VO_3") (pintype "bidirectional"))
    )
    (net (code "45") (name "Net-(LED1-PadA)") (class "Default")
      (node (ref "LED1") (pin "A") (pinfunction "A_A") (pintype "passive"))
      (node (ref "R11") (pin "1") (pinfunction "1_1") (pintype "passive"))
    )
    (net (code "46") (name "Net-(LED2-PadA)") (class "Default")
      (node (ref "LED2") (pin "A") (pinfunction "A_A") (pintype "passive"))
      (node (ref "R8") (pin "1") (pinfunction "1_1") (pintype "passive"))
    )
    (net (code "47") (name "Net-(LED3-PadA)") (class "Default")
      (node (ref "LED3") (pin "A") (pinfunction "A_A") (pintype "passive"))
      (node (ref "R3") (pin "1") (pinfunction "1_1") (pintype "passive"))
    )
    (net (code "48") (name "Net-(LED4-PadA)") (class "Default")
      (node (ref "LED4") (pin "A") (pinfunction "A_A") (pintype "passive"))
      (node (ref "R7") (pin "1") (pinfunction "1_1") (pintype "passive"))
    )
    (net (code "49") (name "Net-(LED5-PadA)") (class "Default")
      (node (ref "LED5") (pin "A") (pinfunction "A_A") (pintype "passive"))
      (node (ref "R6") (pin "1") (pinfunction "1_1") (pintype "passive"))
    )
    (net (code "50") (name "Net-(R9-Pad2)") (class "Default")
      (node (ref "R9") (pin "2") (pinfunction "2_2") (pintype "passive"))
      (node (ref "RX") (pin "A") (pinfunction "A_A") (pintype "passive"))
    )
    (net (code "51") (name "Net-(R10-Pad2)") (class "Default")
      (node (ref "R10") (pin "2") (pinfunction "2_2") (pintype "passive"))
      (node (ref "TX") (pin "A") (pinfunction "A_A") (pintype "passive"))
    )
    (net (code "52") (name "Net-(S1-O)") (class "Default")
      (node (ref "D5") (pin "A") (pinfunction "A_A") (pintype "passive"))
      (node (ref "S1") (pin "1") (pinfunction "O_1") (pintype "passive"))
    )
    (net (code "53") (name "Net-(U$1-A)") (class "Default")
      (node (ref "JP2") (pin "1") (pinfunction "1_1") (pintype "passive"))
      (node (ref "U$1") (pin "15") (pinfunction "A_15") (pintype "power_in"))
    )
    (net (code "54") (name "Net-(U1-PB6(XTAL1{slash}TOSC1))") (class "Default")
      (node (ref "C2") (pin "2") (pinfunction "2_2") (pintype "passive"))
      (node (ref "Q1") (pin "2") (pinfunction "2_2") (pintype "passive"))
      (node (ref "R4") (pin "2") (pinfunction "2_2") (pintype "passive"))
      (node (ref "U1") (pin "9") (pinfunction "PB6(XTAL1/TOSC1)_9") (pintype "bidirectional"))
    )
    (net (code "55") (name "Net-(U1-PB7(XTAL2{slash}TOSC2))") (class "Default")
      (node (ref "C1") (pin "2") (pinfunction "2_2") (pintype "passive"))
      (node (ref "Q1") (pin "1") (pinfunction "1_1") (pintype "passive"))
      (node (ref "R4") (pin "1") (pinfunction "1_1") (pintype "passive"))
      (node (ref "U1") (pin "10") (pinfunction "PB7(XTAL2/TOSC2)_10") (pintype "bidirectional"))
    )
    (net (code "56") (name "unconnected-(FTDI-~{RTS}-Pad3)") (class "Default")
      (node (ref "FTDI") (pin "3") (pinfunction "~{RTS}_3") (pintype "output"))
    )
    (net (code "57") (name "unconnected-(J1-Pad2)") (class "Default")
      (node (ref "J1") (pin "2") (pinfunction "2_2") (pintype "passive"))
    )
    (net (code "58") (name "unconnected-(S1-S-Pad3)") (class "Default")
      (node (ref "S1") (pin "3") (pinfunction "S_3") (pintype "passive"))
    )
    (net (code "59") (name "unconnected-(S3-S-Pad3)") (class "Default")
      (node (ref "S3") (pin "3") (pinfunction "S_3") (pintype "passive"))
    )
    (net (code "60") (name "unconnected-(S4-S-Pad3)") (class "Default")
      (node (ref "S4") (pin "3") (pinfunction "S_3") (pintype "passive"))
    )
    (net (code "61") (name "unconnected-(S5-S-Pad3)") (class "Default")
      (node (ref "S5") (pin "3") (pinfunction "S_3") (pintype "passive"))
    )
    (net (code "62") (name "unconnected-(S6-S-Pad3)") (class "Default")
      (node (ref "S6") (pin "3") (pinfunction "S_3") (pintype "passive"))
    )
    (net (code "63") (name "unconnected-(S7-S-Pad3)") (class "Default")
      (node (ref "S7") (pin "3") (pinfunction "S_3") (pintype "passive"))
    )
    (net (code "64") (name "unconnected-(SV1-Pad8)") (class "Default")
      (node (ref "SV1") (pin "8") (pinfunction "8_8") (pintype "passive"))
    )
    (net (code "65") (name "unconnected-(U1-PC6({slash}RESET)-Pad1)") (class "Default")
      (node (ref "U1") (pin "1") (pinfunction "PC6(/RESET)_1") (pintype "bidirectional"))
    )
  )
)
